# 18650_13s8p.net
KiCad netlist of a schematic drawn in Altium Designer
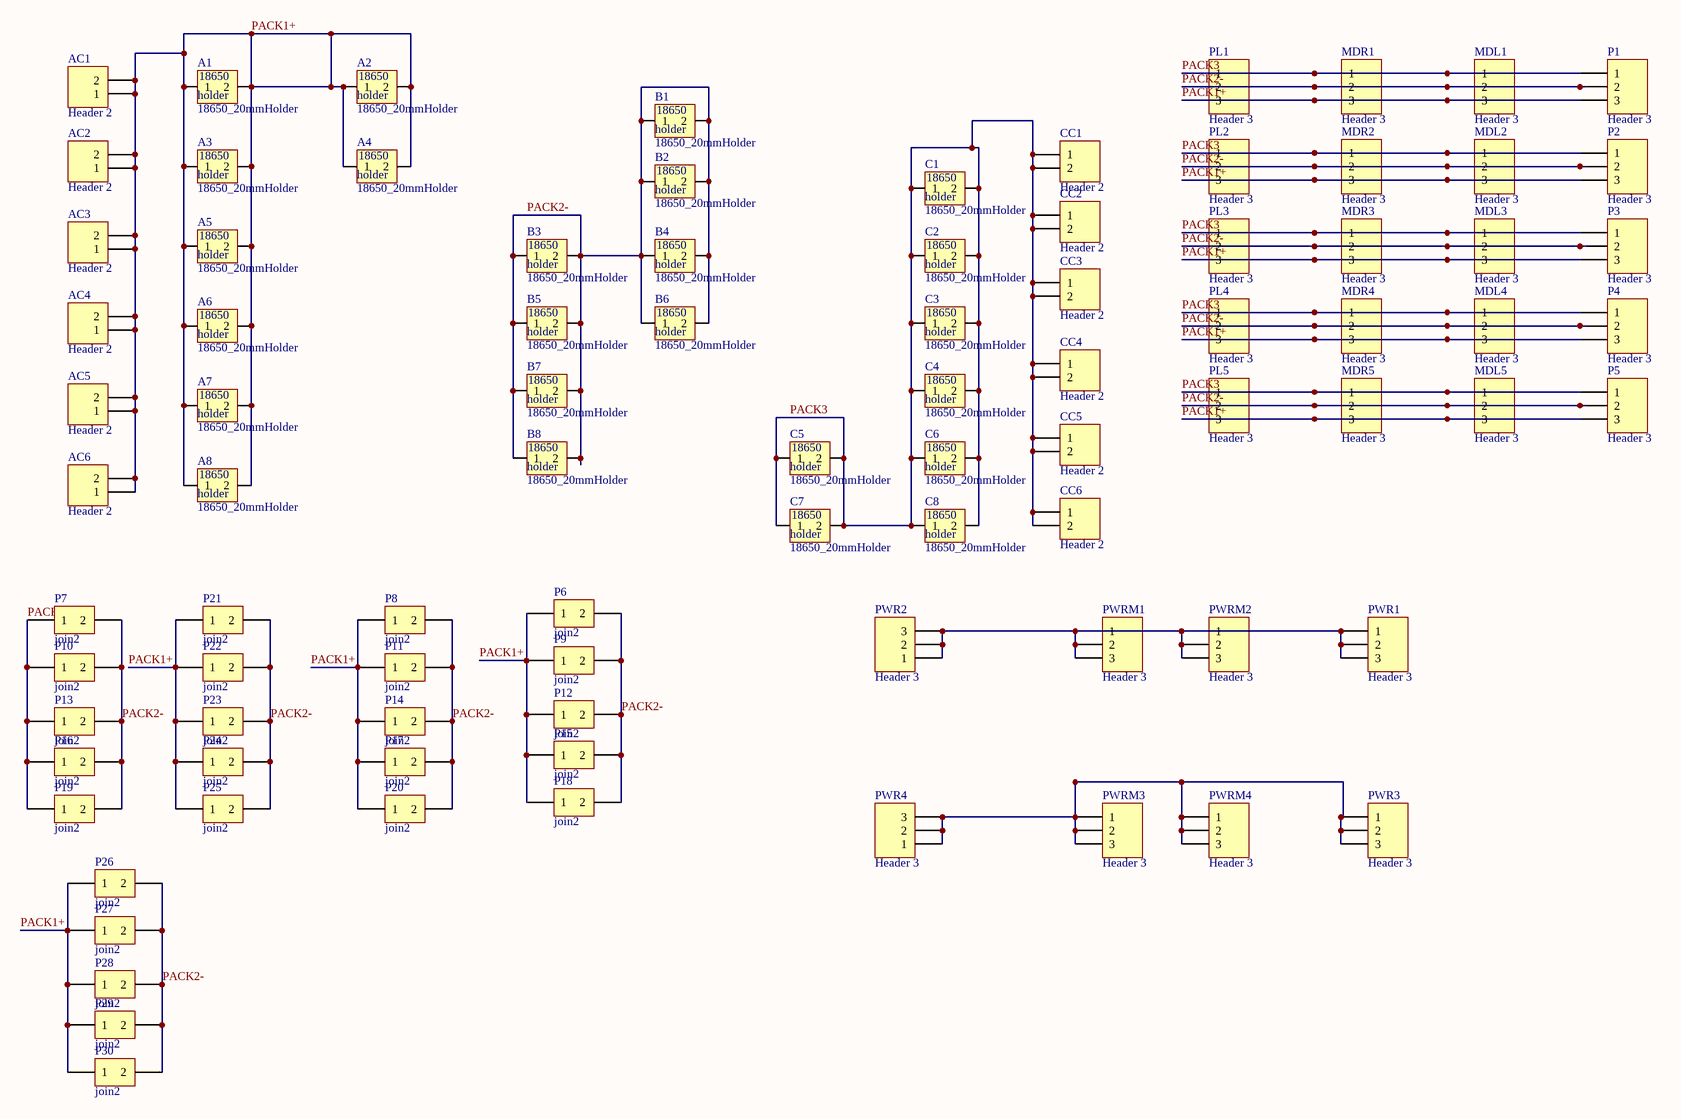
[diagram p0: 18650_13s8p.SchDoc]

(export (version "E")
  (design (tool "Eeschema 10.0.6"))
  (components
    (comp (ref "A1")
      (value "18650_20mmHolder")
      (footprint "18650holder20_2")
      (description "20mm holder 18650 sujungimai tiek - tiek pliuso")
      (fields (field (name "PUBLISHER") "Altium Limited"))
      (libsource (lib "Mechaniniai") (part "18650_20mmHolder"))
    )
    (comp (ref "A2")
      (value "18650_20mmHolder")
      (footprint "18650holder20_2")
      (description "20mm holder 18650 sujungimai tiek - tiek pliuso")
      (fields (field (name "PUBLISHER") "Altium Limited"))
      (libsource (lib "Mechaniniai") (part "18650_20mmHolder"))
    )
    (comp (ref "A3")
      (value "18650_20mmHolder")
      (footprint "18650holder20_2")
      (description "20mm holder 18650 sujungimai tiek - tiek pliuso")
      (fields (field (name "PUBLISHER") "Altium Limited"))
      (libsource (lib "Mechaniniai") (part "18650_20mmHolder"))
    )
    (comp (ref "A4")
      (value "18650_20mmHolder")
      (footprint "18650holder20_2")
      (description "20mm holder 18650 sujungimai tiek - tiek pliuso")
      (fields (field (name "PUBLISHER") "Altium Limited"))
      (libsource (lib "Mechaniniai") (part "18650_20mmHolder"))
    )
    (comp (ref "A5")
      (value "18650_20mmHolder")
      (footprint "18650holder20_2")
      (description "20mm holder 18650 sujungimai tiek - tiek pliuso")
      (fields (field (name "PUBLISHER") "Altium Limited"))
      (libsource (lib "Mechaniniai") (part "18650_20mmHolder"))
    )
    (comp (ref "A6")
      (value "18650_20mmHolder")
      (footprint "18650holder20_2")
      (description "20mm holder 18650 sujungimai tiek - tiek pliuso")
      (fields (field (name "PUBLISHER") "Altium Limited"))
      (libsource (lib "Mechaniniai") (part "18650_20mmHolder"))
    )
    (comp (ref "A7")
      (value "18650_20mmHolder")
      (footprint "18650holder20_2")
      (description "20mm holder 18650 sujungimai tiek - tiek pliuso")
      (fields (field (name "PUBLISHER") "Altium Limited"))
      (libsource (lib "Mechaniniai") (part "18650_20mmHolder"))
    )
    (comp (ref "A8")
      (value "18650_20mmHolder")
      (footprint "18650holder20_2")
      (description "20mm holder 18650 sujungimai tiek - tiek pliuso")
      (fields (field (name "PUBLISHER") "Altium Limited"))
      (libsource (lib "Mechaniniai") (part "18650_20mmHolder"))
    )
    (comp (ref "AC1")
      (value "Header 2")
      (footprint "HDR1X2")
      (description "Header, 2-Pin")
      (fields (field (name "PUBLISHER") "Altium Limited"))
      (libsource (lib "") (part "Header 2_1"))
    )
    (comp (ref "AC2")
      (value "Header 2")
      (footprint "HDR1X2")
      (description "Header, 2-Pin")
      (fields (field (name "PUBLISHER") "Altium Limited"))
      (libsource (lib "") (part "Header 2_1"))
    )
    (comp (ref "AC3")
      (value "Header 2")
      (footprint "HDR1X2")
      (description "Header, 2-Pin")
      (fields (field (name "PUBLISHER") "Altium Limited"))
      (libsource (lib "") (part "Header 2_1"))
    )
    (comp (ref "AC4")
      (value "Header 2")
      (footprint "HDR1X2")
      (description "Header, 2-Pin")
      (fields (field (name "PUBLISHER") "Altium Limited"))
      (libsource (lib "") (part "Header 2_1"))
    )
    (comp (ref "AC5")
      (value "Header 2")
      (footprint "HDR1X2")
      (description "Header, 2-Pin")
      (fields (field (name "PUBLISHER") "Altium Limited"))
      (libsource (lib "") (part "Header 2_1"))
    )
    (comp (ref "AC6")
      (value "Header 2")
      (footprint "HDR1X2")
      (description "Header, 2-Pin")
      (fields (field (name "PUBLISHER") "Altium Limited"))
      (libsource (lib "") (part "Header 2_1"))
    )
    (comp (ref "B1")
      (value "18650_20mmHolder")
      (footprint "18650holder20_2")
      (description "20mm holder 18650 sujungimai tiek - tiek pliuso")
      (fields (field (name "PUBLISHER") "Altium Limited"))
      (libsource (lib "Mechaniniai") (part "18650_20mmHolder"))
    )
    (comp (ref "B2")
      (value "18650_20mmHolder")
      (footprint "18650holder20_2")
      (description "20mm holder 18650 sujungimai tiek - tiek pliuso")
      (fields (field (name "PUBLISHER") "Altium Limited"))
      (libsource (lib "Mechaniniai") (part "18650_20mmHolder"))
    )
    (comp (ref "B3")
      (value "18650_20mmHolder")
      (footprint "18650holder20_2")
      (description "20mm holder 18650 sujungimai tiek - tiek pliuso")
      (fields (field (name "PUBLISHER") "Altium Limited"))
      (libsource (lib "Mechaniniai") (part "18650_20mmHolder"))
    )
    (comp (ref "B4")
      (value "18650_20mmHolder")
      (footprint "18650holder20_2")
      (description "20mm holder 18650 sujungimai tiek - tiek pliuso")
      (fields (field (name "PUBLISHER") "Altium Limited"))
      (libsource (lib "Mechaniniai") (part "18650_20mmHolder"))
    )
    (comp (ref "B5")
      (value "18650_20mmHolder")
      (footprint "18650holder20_2")
      (description "20mm holder 18650 sujungimai tiek - tiek pliuso")
      (fields (field (name "PUBLISHER") "Altium Limited"))
      (libsource (lib "Mechaniniai") (part "18650_20mmHolder"))
    )
    (comp (ref "B6")
      (value "18650_20mmHolder")
      (footprint "18650holder20_2")
      (description "20mm holder 18650 sujungimai tiek - tiek pliuso")
      (fields (field (name "PUBLISHER") "Altium Limited"))
      (libsource (lib "Mechaniniai") (part "18650_20mmHolder"))
    )
    (comp (ref "B7")
      (value "18650_20mmHolder")
      (footprint "18650holder20_2")
      (description "20mm holder 18650 sujungimai tiek - tiek pliuso")
      (fields (field (name "PUBLISHER") "Altium Limited"))
      (libsource (lib "Mechaniniai") (part "18650_20mmHolder"))
    )
    (comp (ref "B8")
      (value "18650_20mmHolder")
      (footprint "18650holder20_2")
      (description "20mm holder 18650 sujungimai tiek - tiek pliuso")
      (fields (field (name "PUBLISHER") "Altium Limited"))
      (libsource (lib "Mechaniniai") (part "18650_20mmHolder"))
    )
    (comp (ref "C1")
      (value "18650_20mmHolder")
      (footprint "18650holder20_2")
      (description "20mm holder 18650 sujungimai tiek - tiek pliuso")
      (fields (field (name "PUBLISHER") "Altium Limited"))
      (libsource (lib "Mechaniniai") (part "18650_20mmHolder"))
    )
    (comp (ref "C2")
      (value "18650_20mmHolder")
      (footprint "18650holder20_2")
      (description "20mm holder 18650 sujungimai tiek - tiek pliuso")
      (fields (field (name "PUBLISHER") "Altium Limited"))
      (libsource (lib "Mechaniniai") (part "18650_20mmHolder"))
    )
    (comp (ref "C3")
      (value "18650_20mmHolder")
      (footprint "18650holder20_2")
      (description "20mm holder 18650 sujungimai tiek - tiek pliuso")
      (fields (field (name "PUBLISHER") "Altium Limited"))
      (libsource (lib "Mechaniniai") (part "18650_20mmHolder"))
    )
    (comp (ref "C4")
      (value "18650_20mmHolder")
      (footprint "18650holder20_2")
      (description "20mm holder 18650 sujungimai tiek - tiek pliuso")
      (fields (field (name "PUBLISHER") "Altium Limited"))
      (libsource (lib "Mechaniniai") (part "18650_20mmHolder"))
    )
    (comp (ref "C5")
      (value "18650_20mmHolder")
      (footprint "18650holder20_2")
      (description "20mm holder 18650 sujungimai tiek - tiek pliuso")
      (fields (field (name "PUBLISHER") "Altium Limited"))
      (libsource (lib "Mechaniniai") (part "18650_20mmHolder"))
    )
    (comp (ref "C6")
      (value "18650_20mmHolder")
      (footprint "18650holder20_2")
      (description "20mm holder 18650 sujungimai tiek - tiek pliuso")
      (fields (field (name "PUBLISHER") "Altium Limited"))
      (libsource (lib "Mechaniniai") (part "18650_20mmHolder"))
    )
    (comp (ref "C7")
      (value "18650_20mmHolder")
      (footprint "18650holder20_2")
      (description "20mm holder 18650 sujungimai tiek - tiek pliuso")
      (fields (field (name "PUBLISHER") "Altium Limited"))
      (libsource (lib "Mechaniniai") (part "18650_20mmHolder"))
    )
    (comp (ref "C8")
      (value "18650_20mmHolder")
      (footprint "18650holder20_2")
      (description "20mm holder 18650 sujungimai tiek - tiek pliuso")
      (fields (field (name "PUBLISHER") "Altium Limited"))
      (libsource (lib "Mechaniniai") (part "18650_20mmHolder"))
    )
    (comp (ref "CC1")
      (value "Header 2")
      (footprint "HDR1X2")
      (description "Header, 2-Pin")
      (fields (field (name "PUBLISHER") "Altium Limited"))
      (libsource (lib "PIN_HEADER") (part "Header 2"))
    )
    (comp (ref "CC2")
      (value "Header 2")
      (footprint "HDR1X2")
      (description "Header, 2-Pin")
      (fields (field (name "PUBLISHER") "Altium Limited"))
      (libsource (lib "PIN_HEADER") (part "Header 2"))
    )
    (comp (ref "CC3")
      (value "Header 2")
      (footprint "HDR1X2")
      (description "Header, 2-Pin")
      (fields (field (name "PUBLISHER") "Altium Limited"))
      (libsource (lib "PIN_HEADER") (part "Header 2"))
    )
    (comp (ref "CC4")
      (value "Header 2")
      (footprint "HDR1X2")
      (description "Header, 2-Pin")
      (fields (field (name "PUBLISHER") "Altium Limited"))
      (libsource (lib "PIN_HEADER") (part "Header 2"))
    )
    (comp (ref "CC5")
      (value "Header 2")
      (footprint "HDR1X2")
      (description "Header, 2-Pin")
      (fields (field (name "PUBLISHER") "Altium Limited"))
      (libsource (lib "PIN_HEADER") (part "Header 2"))
    )
    (comp (ref "CC6")
      (value "Header 2")
      (footprint "HDR1X2")
      (description "Header, 2-Pin")
      (fields (field (name "PUBLISHER") "Altium Limited"))
      (libsource (lib "PIN_HEADER") (part "Header 2"))
    )
    (comp (ref "MDL1")
      (value "Header 3")
      (footprint "HDR1X3")
      (description "Header, 3-Pin")
      (fields (field (name "PUBLISHER") "Altium Limited"))
      (libsource (lib "PIN_HEADER") (part "Header 3"))
    )
    (comp (ref "MDL2")
      (value "Header 3")
      (footprint "HDR1X3")
      (description "Header, 3-Pin")
      (fields (field (name "PUBLISHER") "Altium Limited"))
      (libsource (lib "PIN_HEADER") (part "Header 3"))
    )
    (comp (ref "MDL3")
      (value "Header 3")
      (footprint "HDR1X3")
      (description "Header, 3-Pin")
      (fields (field (name "PUBLISHER") "Altium Limited"))
      (libsource (lib "PIN_HEADER") (part "Header 3"))
    )
    (comp (ref "MDL4")
      (value "Header 3")
      (footprint "HDR1X3")
      (description "Header, 3-Pin")
      (fields (field (name "PUBLISHER") "Altium Limited"))
      (libsource (lib "PIN_HEADER") (part "Header 3"))
    )
    (comp (ref "MDL5")
      (value "Header 3")
      (footprint "HDR1X3")
      (description "Header, 3-Pin")
      (fields (field (name "PUBLISHER") "Altium Limited"))
      (libsource (lib "PIN_HEADER") (part "Header 3"))
    )
    (comp (ref "MDR1")
      (value "Header 3")
      (footprint "HDR1X3")
      (description "Header, 3-Pin")
      (fields (field (name "PUBLISHER") "Altium Limited"))
      (libsource (lib "PIN_HEADER") (part "Header 3"))
    )
    (comp (ref "MDR2")
      (value "Header 3")
      (footprint "HDR1X3")
      (description "Header, 3-Pin")
      (fields (field (name "PUBLISHER") "Altium Limited"))
      (libsource (lib "PIN_HEADER") (part "Header 3"))
    )
    (comp (ref "MDR3")
      (value "Header 3")
      (footprint "HDR1X3")
      (description "Header, 3-Pin")
      (fields (field (name "PUBLISHER") "Altium Limited"))
      (libsource (lib "PIN_HEADER") (part "Header 3"))
    )
    (comp (ref "MDR4")
      (value "Header 3")
      (footprint "HDR1X3")
      (description "Header, 3-Pin")
      (fields (field (name "PUBLISHER") "Altium Limited"))
      (libsource (lib "PIN_HEADER") (part "Header 3"))
    )
    (comp (ref "MDR5")
      (value "Header 3")
      (footprint "HDR1X3")
      (description "Header, 3-Pin")
      (fields (field (name "PUBLISHER") "Altium Limited"))
      (libsource (lib "PIN_HEADER") (part "Header 3"))
    )
    (comp (ref "P1")
      (value "Header 3")
      (footprint "HDR1X3")
      (description "Header, 3-Pin")
      (fields (field (name "PUBLISHER") "Altium Limited"))
      (libsource (lib "PIN_HEADER") (part "Header 3"))
    )
    (comp (ref "P2")
      (value "Header 3")
      (footprint "HDR1X3")
      (description "Header, 3-Pin")
      (fields (field (name "PUBLISHER") "Altium Limited"))
      (libsource (lib "PIN_HEADER") (part "Header 3"))
    )
    (comp (ref "P3")
      (value "Header 3")
      (footprint "HDR1X3")
      (description "Header, 3-Pin")
      (fields (field (name "PUBLISHER") "Altium Limited"))
      (libsource (lib "PIN_HEADER") (part "Header 3"))
    )
    (comp (ref "P4")
      (value "Header 3")
      (footprint "HDR1X3")
      (description "Header, 3-Pin")
      (fields (field (name "PUBLISHER") "Altium Limited"))
      (libsource (lib "PIN_HEADER") (part "Header 3"))
    )
    (comp (ref "P5")
      (value "Header 3")
      (footprint "HDR1X3")
      (description "Header, 3-Pin")
      (fields (field (name "PUBLISHER") "Altium Limited"))
      (libsource (lib "PIN_HEADER") (part "Header 3"))
    )
    (comp (ref "P6")
      (value "join2")
      (footprint "join2_0603")
      (description "Header, 2-Pin")
      (fields (field (name "PUBLISHER") "Altium Limited"))
      (libsource (lib "PIN_HEADER") (part "join2"))
    )
    (comp (ref "P7")
      (value "join2")
      (footprint "join2_0603")
      (description "Header, 2-Pin")
      (fields (field (name "PUBLISHER") "Altium Limited"))
      (libsource (lib "PIN_HEADER") (part "join2"))
    )
    (comp (ref "P8")
      (value "join2")
      (footprint "join2_0603")
      (description "Header, 2-Pin")
      (fields (field (name "PUBLISHER") "Altium Limited"))
      (libsource (lib "PIN_HEADER") (part "join2"))
    )
    (comp (ref "P9")
      (value "join2")
      (footprint "join2_0603")
      (description "Header, 2-Pin")
      (fields (field (name "PUBLISHER") "Altium Limited"))
      (libsource (lib "PIN_HEADER") (part "join2"))
    )
    (comp (ref "P10")
      (value "join2")
      (footprint "join2_0603")
      (description "Header, 2-Pin")
      (fields (field (name "PUBLISHER") "Altium Limited"))
      (libsource (lib "PIN_HEADER") (part "join2"))
    )
    (comp (ref "P11")
      (value "join2")
      (footprint "join2_0603")
      (description "Header, 2-Pin")
      (fields (field (name "PUBLISHER") "Altium Limited"))
      (libsource (lib "PIN_HEADER") (part "join2"))
    )
    (comp (ref "P12")
      (value "join2")
      (footprint "join2_0603")
      (description "Header, 2-Pin")
      (fields (field (name "PUBLISHER") "Altium Limited"))
      (libsource (lib "PIN_HEADER") (part "join2"))
    )
    (comp (ref "P13")
      (value "join2")
      (footprint "join2_0603")
      (description "Header, 2-Pin")
      (fields (field (name "PUBLISHER") "Altium Limited"))
      (libsource (lib "PIN_HEADER") (part "join2"))
    )
    (comp (ref "P14")
      (value "join2")
      (footprint "join2_0603")
      (description "Header, 2-Pin")
      (fields (field (name "PUBLISHER") "Altium Limited"))
      (libsource (lib "PIN_HEADER") (part "join2"))
    )
    (comp (ref "P15")
      (value "join2")
      (footprint "join2_0603")
      (description "Header, 2-Pin")
      (fields (field (name "PUBLISHER") "Altium Limited"))
      (libsource (lib "PIN_HEADER") (part "join2"))
    )
    (comp (ref "P16")
      (value "join2")
      (footprint "join2_0603")
      (description "Header, 2-Pin")
      (fields (field (name "PUBLISHER") "Altium Limited"))
      (libsource (lib "PIN_HEADER") (part "join2"))
    )
    (comp (ref "P17")
      (value "join2")
      (footprint "join2_0603")
      (description "Header, 2-Pin")
      (fields (field (name "PUBLISHER") "Altium Limited"))
      (libsource (lib "PIN_HEADER") (part "join2"))
    )
    (comp (ref "P18")
      (value "join2")
      (footprint "join2_0603")
      (description "Header, 2-Pin")
      (fields (field (name "PUBLISHER") "Altium Limited"))
      (libsource (lib "PIN_HEADER") (part "join2"))
    )
    (comp (ref "P19")
      (value "join2")
      (footprint "join2_0603")
      (description "Header, 2-Pin")
      (fields (field (name "PUBLISHER") "Altium Limited"))
      (libsource (lib "PIN_HEADER") (part "join2"))
    )
    (comp (ref "P20")
      (value "join2")
      (footprint "join2_0603")
      (description "Header, 2-Pin")
      (fields (field (name "PUBLISHER") "Altium Limited"))
      (libsource (lib "PIN_HEADER") (part "join2"))
    )
    (comp (ref "P21")
      (value "join2")
      (footprint "join2_0603")
      (description "Header, 2-Pin")
      (fields (field (name "PUBLISHER") "Altium Limited"))
      (libsource (lib "PIN_HEADER") (part "join2"))
    )
    (comp (ref "P22")
      (value "join2")
      (footprint "join2_0603")
      (description "Header, 2-Pin")
      (fields (field (name "PUBLISHER") "Altium Limited"))
      (libsource (lib "PIN_HEADER") (part "join2"))
    )
    (comp (ref "P23")
      (value "join2")
      (footprint "join2_0603")
      (description "Header, 2-Pin")
      (fields (field (name "PUBLISHER") "Altium Limited"))
      (libsource (lib "PIN_HEADER") (part "join2"))
    )
    (comp (ref "P24")
      (value "join2")
      (footprint "join2_0603")
      (description "Header, 2-Pin")
      (fields (field (name "PUBLISHER") "Altium Limited"))
      (libsource (lib "PIN_HEADER") (part "join2"))
    )
    (comp (ref "P25")
      (value "join2")
      (footprint "join2_0603")
      (description "Header, 2-Pin")
      (fields (field (name "PUBLISHER") "Altium Limited"))
      (libsource (lib "PIN_HEADER") (part "join2"))
    )
    (comp (ref "P26")
      (value "join2")
      (footprint "join2_0603")
      (description "Header, 2-Pin")
      (fields (field (name "PUBLISHER") "Altium Limited"))
      (libsource (lib "PIN_HEADER") (part "join2"))
    )
    (comp (ref "P27")
      (value "join2")
      (footprint "join2_0603")
      (description "Header, 2-Pin")
      (fields (field (name "PUBLISHER") "Altium Limited"))
      (libsource (lib "PIN_HEADER") (part "join2"))
    )
    (comp (ref "P28")
      (value "join2")
      (footprint "join2_0603")
      (description "Header, 2-Pin")
      (fields (field (name "PUBLISHER") "Altium Limited"))
      (libsource (lib "PIN_HEADER") (part "join2"))
    )
    (comp (ref "P29")
      (value "join2")
      (footprint "join2_0603")
      (description "Header, 2-Pin")
      (fields (field (name "PUBLISHER") "Altium Limited"))
      (libsource (lib "PIN_HEADER") (part "join2"))
    )
    (comp (ref "P30")
      (value "join2")
      (footprint "join2_0603")
      (description "Header, 2-Pin")
      (fields (field (name "PUBLISHER") "Altium Limited"))
      (libsource (lib "PIN_HEADER") (part "join2"))
    )
    (comp (ref "PL1")
      (value "Header 3")
      (footprint "HDR1X3")
      (description "Header, 3-Pin")
      (fields (field (name "PUBLISHER") "Altium Limited"))
      (libsource (lib "PIN_HEADER") (part "Header 3"))
    )
    (comp (ref "PL2")
      (value "Header 3")
      (footprint "HDR1X3")
      (description "Header, 3-Pin")
      (fields (field (name "PUBLISHER") "Altium Limited"))
      (libsource (lib "PIN_HEADER") (part "Header 3"))
    )
    (comp (ref "PL3")
      (value "Header 3")
      (footprint "HDR1X3")
      (description "Header, 3-Pin")
      (fields (field (name "PUBLISHER") "Altium Limited"))
      (libsource (lib "PIN_HEADER") (part "Header 3"))
    )
    (comp (ref "PL4")
      (value "Header 3")
      (footprint "HDR1X3")
      (description "Header, 3-Pin")
      (fields (field (name "PUBLISHER") "Altium Limited"))
      (libsource (lib "PIN_HEADER") (part "Header 3"))
    )
    (comp (ref "PL5")
      (value "Header 3")
      (footprint "HDR1X3")
      (description "Header, 3-Pin")
      (fields (field (name "PUBLISHER") "Altium Limited"))
      (libsource (lib "PIN_HEADER") (part "Header 3"))
    )
    (comp (ref "PWR1")
      (value "Header 3")
      (footprint "HDR1X3")
      (description "Header, 3-Pin")
      (fields (field (name "PUBLISHER") "Altium Limited"))
      (libsource (lib "PIN_HEADER") (part "Header 3"))
    )
    (comp (ref "PWR2")
      (value "Header 3")
      (footprint "HDR1X3")
      (description "Header, 3-Pin")
      (fields (field (name "PUBLISHER") "Altium Limited"))
      (libsource (lib "") (part "Header 3_1"))
    )
    (comp (ref "PWR3")
      (value "Header 3")
      (footprint "HDR1X3")
      (description "Header, 3-Pin")
      (fields (field (name "PUBLISHER") "Altium Limited"))
      (libsource (lib "PIN_HEADER") (part "Header 3"))
    )
    (comp (ref "PWR4")
      (value "Header 3")
      (footprint "HDR1X3")
      (description "Header, 3-Pin")
      (fields (field (name "PUBLISHER") "Altium Limited"))
      (libsource (lib "") (part "Header 3_1"))
    )
    (comp (ref "PWRM1")
      (value "Header 3")
      (footprint "HDR1X3")
      (description "Header, 3-Pin")
      (fields (field (name "PUBLISHER") "Altium Limited"))
      (libsource (lib "PIN_HEADER") (part "Header 3"))
    )
    (comp (ref "PWRM2")
      (value "Header 3")
      (footprint "HDR1X3")
      (description "Header, 3-Pin")
      (fields (field (name "PUBLISHER") "Altium Limited"))
      (libsource (lib "PIN_HEADER") (part "Header 3"))
    )
    (comp (ref "PWRM3")
      (value "Header 3")
      (footprint "HDR1X3")
      (description "Header, 3-Pin")
      (fields (field (name "PUBLISHER") "Altium Limited"))
      (libsource (lib "PIN_HEADER") (part "Header 3"))
    )
    (comp (ref "PWRM4")
      (value "Header 3")
      (footprint "HDR1X3")
      (description "Header, 3-Pin")
      (fields (field (name "PUBLISHER") "Altium Limited"))
      (libsource (lib "PIN_HEADER") (part "Header 3"))
    )
  )
  (nets
    (net (code "1") (name "/PACK1+") (class "Default")
      (node (ref "A1") (pin "1") (pinfunction "1_1") (pintype "passive"))
      (node (ref "A1") (pin "2") (pinfunction "2_2") (pintype "passive"))
      (node (ref "A2") (pin "1") (pinfunction "1_1") (pintype "passive"))
      (node (ref "A2") (pin "2") (pinfunction "2_2") (pintype "passive"))
      (node (ref "A3") (pin "1") (pinfunction "1_1") (pintype "passive"))
      (node (ref "A3") (pin "2") (pinfunction "2_2") (pintype "passive"))
      (node (ref "A4") (pin "1") (pinfunction "1_1") (pintype "passive"))
      (node (ref "A4") (pin "2") (pinfunction "2_2") (pintype "passive"))
      (node (ref "A5") (pin "1") (pinfunction "1_1") (pintype "passive"))
      (node (ref "A5") (pin "2") (pinfunction "2_2") (pintype "passive"))
      (node (ref "A6") (pin "1") (pinfunction "1_1") (pintype "passive"))
      (node (ref "A6") (pin "2") (pinfunction "2_2") (pintype "passive"))
      (node (ref "A7") (pin "1") (pinfunction "1_1") (pintype "passive"))
      (node (ref "A7") (pin "2") (pinfunction "2_2") (pintype "passive"))
      (node (ref "A8") (pin "1") (pinfunction "1_1") (pintype "passive"))
      (node (ref "A8") (pin "2") (pinfunction "2_2") (pintype "passive"))
      (node (ref "AC1") (pin "1") (pinfunction "1_1") (pintype "passive"))
      (node (ref "AC1") (pin "2") (pinfunction "2_2") (pintype "passive"))
      (node (ref "AC2") (pin "1") (pinfunction "1_1") (pintype "passive"))
      (node (ref "AC2") (pin "2") (pinfunction "2_2") (pintype "passive"))
      (node (ref "AC3") (pin "1") (pinfunction "1_1") (pintype "passive"))
      (node (ref "AC3") (pin "2") (pinfunction "2_2") (pintype "passive"))
      (node (ref "AC4") (pin "1") (pinfunction "1_1") (pintype "passive"))
      (node (ref "AC4") (pin "2") (pinfunction "2_2") (pintype "passive"))
      (node (ref "AC5") (pin "1") (pinfunction "1_1") (pintype "passive"))
      (node (ref "AC5") (pin "2") (pinfunction "2_2") (pintype "passive"))
      (node (ref "AC6") (pin "1") (pinfunction "1_1") (pintype "passive"))
      (node (ref "AC6") (pin "2") (pinfunction "2_2") (pintype "passive"))
      (node (ref "MDL1") (pin "3") (pinfunction "3_3") (pintype "passive"))
      (node (ref "MDL2") (pin "3") (pinfunction "3_3") (pintype "passive"))
      (node (ref "MDL3") (pin "3") (pinfunction "3_3") (pintype "passive"))
      (node (ref "MDL4") (pin "3") (pinfunction "3_3") (pintype "passive"))
      (node (ref "MDL5") (pin "3") (pinfunction "3_3") (pintype "passive"))
      (node (ref "MDR1") (pin "3") (pinfunction "3_3") (pintype "passive"))
      (node (ref "MDR2") (pin "3") (pinfunction "3_3") (pintype "passive"))
      (node (ref "MDR3") (pin "3") (pinfunction "3_3") (pintype "passive"))
      (node (ref "MDR4") (pin "3") (pinfunction "3_3") (pintype "passive"))
      (node (ref "MDR5") (pin "3") (pinfunction "3_3") (pintype "passive"))
      (node (ref "P1") (pin "3") (pinfunction "3_3") (pintype "passive"))
      (node (ref "P10") (pin "1") (pinfunction "1_1") (pintype "passive"))
      (node (ref "P11") (pin "1") (pinfunction "1_1") (pintype "passive"))
      (node (ref "P12") (pin "1") (pinfunction "1_1") (pintype "passive"))
      (node (ref "P13") (pin "1") (pinfunction "1_1") (pintype "passive"))
      (node (ref "P14") (pin "1") (pinfunction "1_1") (pintype "passive"))
      (node (ref "P15") (pin "1") (pinfunction "1_1") (pintype "passive"))
      (node (ref "P16") (pin "1") (pinfunction "1_1") (pintype "passive"))
      (node (ref "P17") (pin "1") (pinfunction "1_1") (pintype "passive"))
      (node (ref "P18") (pin "1") (pinfunction "1_1") (pintype "passive"))
      (node (ref "P19") (pin "1") (pinfunction "1_1") (pintype "passive"))
      (node (ref "P2") (pin "3") (pinfunction "3_3") (pintype "passive"))
      (node (ref "P20") (pin "1") (pinfunction "1_1") (pintype "passive"))
      (node (ref "P21") (pin "1") (pinfunction "1_1") (pintype "passive"))
      (node (ref "P22") (pin "1") (pinfunction "1_1") (pintype "passive"))
      (node (ref "P23") (pin "1") (pinfunction "1_1") (pintype "passive"))
      (node (ref "P24") (pin "1") (pinfunction "1_1") (pintype "passive"))
      (node (ref "P25") (pin "1") (pinfunction "1_1") (pintype "passive"))
      (node (ref "P26") (pin "1") (pinfunction "1_1") (pintype "passive"))
      (node (ref "P27") (pin "1") (pinfunction "1_1") (pintype "passive"))
      (node (ref "P28") (pin "1") (pinfunction "1_1") (pintype "passive"))
      (node (ref "P29") (pin "1") (pinfunction "1_1") (pintype "passive"))
      (node (ref "P3") (pin "3") (pinfunction "3_3") (pintype "passive"))
      (node (ref "P30") (pin "1") (pinfunction "1_1") (pintype "passive"))
      (node (ref "P4") (pin "3") (pinfunction "3_3") (pintype "passive"))
      (node (ref "P5") (pin "3") (pinfunction "3_3") (pintype "passive"))
      (node (ref "P6") (pin "1") (pinfunction "1_1") (pintype "passive"))
      (node (ref "P7") (pin "1") (pinfunction "1_1") (pintype "passive"))
      (node (ref "P8") (pin "1") (pinfunction "1_1") (pintype "passive"))
      (node (ref "P9") (pin "1") (pinfunction "1_1") (pintype "passive"))
      (node (ref "PL1") (pin "3") (pinfunction "3_3") (pintype "passive"))
      (node (ref "PL2") (pin "3") (pinfunction "3_3") (pintype "passive"))
      (node (ref "PL3") (pin "3") (pinfunction "3_3") (pintype "passive"))
      (node (ref "PL4") (pin "3") (pinfunction "3_3") (pintype "passive"))
      (node (ref "PL5") (pin "3") (pinfunction "3_3") (pintype "passive"))
    )
    (net (code "2") (name "/PACK2-") (class "Default")
      (node (ref "B1") (pin "1") (pinfunction "1_1") (pintype "passive"))
      (node (ref "B1") (pin "2") (pinfunction "2_2") (pintype "passive"))
      (node (ref "B2") (pin "1") (pinfunction "1_1") (pintype "passive"))
      (node (ref "B2") (pin "2") (pinfunction "2_2") (pintype "passive"))
      (node (ref "B3") (pin "1") (pinfunction "1_1") (pintype "passive"))
      (node (ref "B3") (pin "2") (pinfunction "2_2") (pintype "passive"))
      (node (ref "B4") (pin "1") (pinfunction "1_1") (pintype "passive"))
      (node (ref "B4") (pin "2") (pinfunction "2_2") (pintype "passive"))
      (node (ref "B5") (pin "1") (pinfunction "1_1") (pintype "passive"))
      (node (ref "B5") (pin "2") (pinfunction "2_2") (pintype "passive"))
      (node (ref "B6") (pin "1") (pinfunction "1_1") (pintype "passive"))
      (node (ref "B6") (pin "2") (pinfunction "2_2") (pintype "passive"))
      (node (ref "B7") (pin "1") (pinfunction "1_1") (pintype "passive"))
      (node (ref "B7") (pin "2") (pinfunction "2_2") (pintype "passive"))
      (node (ref "B8") (pin "1") (pinfunction "1_1") (pintype "passive"))
      (node (ref "B8") (pin "2") (pinfunction "2_2") (pintype "passive"))
      (node (ref "MDL1") (pin "2") (pinfunction "2_2") (pintype "passive"))
      (node (ref "MDL2") (pin "2") (pinfunction "2_2") (pintype "passive"))
      (node (ref "MDL3") (pin "2") (pinfunction "2_2") (pintype "passive"))
      (node (ref "MDL4") (pin "2") (pinfunction "2_2") (pintype "passive"))
      (node (ref "MDL5") (pin "2") (pinfunction "2_2") (pintype "passive"))
      (node (ref "MDR1") (pin "2") (pinfunction "2_2") (pintype "passive"))
      (node (ref "MDR2") (pin "2") (pinfunction "2_2") (pintype "passive"))
      (node (ref "MDR3") (pin "2") (pinfunction "2_2") (pintype "passive"))
      (node (ref "MDR4") (pin "2") (pinfunction "2_2") (pintype "passive"))
      (node (ref "MDR5") (pin "2") (pinfunction "2_2") (pintype "passive"))
      (node (ref "P1") (pin "2") (pinfunction "2_2") (pintype "passive"))
      (node (ref "P10") (pin "2") (pinfunction "2_2") (pintype "passive"))
      (node (ref "P11") (pin "2") (pinfunction "2_2") (pintype "passive"))
      (node (ref "P12") (pin "2") (pinfunction "2_2") (pintype "passive"))
      (node (ref "P13") (pin "2") (pinfunction "2_2") (pintype "passive"))
      (node (ref "P14") (pin "2") (pinfunction "2_2") (pintype "passive"))
      (node (ref "P15") (pin "2") (pinfunction "2_2") (pintype "passive"))
      (node (ref "P16") (pin "2") (pinfunction "2_2") (pintype "passive"))
      (node (ref "P17") (pin "2") (pinfunction "2_2") (pintype "passive"))
      (node (ref "P18") (pin "2") (pinfunction "2_2") (pintype "passive"))
      (node (ref "P19") (pin "2") (pinfunction "2_2") (pintype "passive"))
      (node (ref "P2") (pin "2") (pinfunction "2_2") (pintype "passive"))
      (node (ref "P20") (pin "2") (pinfunction "2_2") (pintype "passive"))
      (node (ref "P21") (pin "2") (pinfunction "2_2") (pintype "passive"))
      (node (ref "P22") (pin "2") (pinfunction "2_2") (pintype "passive"))
      (node (ref "P23") (pin "2") (pinfunction "2_2") (pintype "passive"))
      (node (ref "P24") (pin "2") (pinfunction "2_2") (pintype "passive"))
      (node (ref "P25") (pin "2") (pinfunction "2_2") (pintype "passive"))
      (node (ref "P26") (pin "2") (pinfunction "2_2") (pintype "passive"))
      (node (ref "P27") (pin "2") (pinfunction "2_2") (pintype "passive"))
      (node (ref "P28") (pin "2") (pinfunction "2_2") (pintype "passive"))
      (node (ref "P29") (pin "2") (pinfunction "2_2") (pintype "passive"))
      (node (ref "P3") (pin "2") (pinfunction "2_2") (pintype "passive"))
      (node (ref "P30") (pin "2") (pinfunction "2_2") (pintype "passive"))
      (node (ref "P4") (pin "2") (pinfunction "2_2") (pintype "passive"))
      (node (ref "P5") (pin "2") (pinfunction "2_2") (pintype "passive"))
      (node (ref "P6") (pin "2") (pinfunction "2_2") (pintype "passive"))
      (node (ref "P7") (pin "2") (pinfunction "2_2") (pintype "passive"))
      (node (ref "P8") (pin "2") (pinfunction "2_2") (pintype "passive"))
      (node (ref "P9") (pin "2") (pinfunction "2_2") (pintype "passive"))
      (node (ref "PL1") (pin "2") (pinfunction "2_2") (pintype "passive"))
      (node (ref "PL2") (pin "2") (pinfunction "2_2") (pintype "passive"))
      (node (ref "PL3") (pin "2") (pinfunction "2_2") (pintype "passive"))
      (node (ref "PL4") (pin "2") (pinfunction "2_2") (pintype "passive"))
      (node (ref "PL5") (pin "2") (pinfunction "2_2") (pintype "passive"))
    )
    (net (code "3") (name "/PACK3") (class "Default")
      (node (ref "C1") (pin "1") (pinfunction "1_1") (pintype "passive"))
      (node (ref "C1") (pin "2") (pinfunction "2_2") (pintype "passive"))
      (node (ref "C2") (pin "1") (pinfunction "1_1") (pintype "passive"))
      (node (ref "C2") (pin "2") (pinfunction "2_2") (pintype "passive"))
      (node (ref "C3") (pin "1") (pinfunction "1_1") (pintype "passive"))
      (node (ref "C3") (pin "2") (pinfunction "2_2") (pintype "passive"))
      (node (ref "C4") (pin "1") (pinfunction "1_1") (pintype "passive"))
      (node (ref "C4") (pin "2") (pinfunction "2_2") (pintype "passive"))
      (node (ref "C5") (pin "1") (pinfunction "1_1") (pintype "passive"))
      (node (ref "C5") (pin "2") (pinfunction "2_2") (pintype "passive"))
      (node (ref "C6") (pin "1") (pinfunction "1_1") (pintype "passive"))
      (node (ref "C6") (pin "2") (pinfunction "2_2") (pintype "passive"))
      (node (ref "C7") (pin "1") (pinfunction "1_1") (pintype "passive"))
      (node (ref "C7") (pin "2") (pinfunction "2_2") (pintype "passive"))
      (node (ref "C8") (pin "1") (pinfunction "1_1") (pintype "passive"))
      (node (ref "C8") (pin "2") (pinfunction "2_2") (pintype "passive"))
      (node (ref "CC1") (pin "1") (pinfunction "1_1") (pintype "passive"))
      (node (ref "CC1") (pin "2") (pinfunction "2_2") (pintype "passive"))
      (node (ref "CC2") (pin "1") (pinfunction "1_1") (pintype "passive"))
      (node (ref "CC2") (pin "2") (pinfunction "2_2") (pintype "passive"))
      (node (ref "CC3") (pin "1") (pinfunction "1_1") (pintype "passive"))
      (node (ref "CC3") (pin "2") (pinfunction "2_2") (pintype "passive"))
      (node (ref "CC4") (pin "1") (pinfunction "1_1") (pintype "passive"))
      (node (ref "CC4") (pin "2") (pinfunction "2_2") (pintype "passive"))
      (node (ref "CC5") (pin "1") (pinfunction "1_1") (pintype "passive"))
      (node (ref "CC5") (pin "2") (pinfunction "2_2") (pintype "passive"))
      (node (ref "CC6") (pin "1") (pinfunction "1_1") (pintype "passive"))
      (node (ref "CC6") (pin "2") (pinfunction "2_2") (pintype "passive"))
      (node (ref "MDL1") (pin "1") (pinfunction "1_1") (pintype "passive"))
      (node (ref "MDL2") (pin "1") (pinfunction "1_1") (pintype "passive"))
      (node (ref "MDL3") (pin "1") (pinfunction "1_1") (pintype "passive"))
      (node (ref "MDL4") (pin "1") (pinfunction "1_1") (pintype "passive"))
      (node (ref "MDL5") (pin "1") (pinfunction "1_1") (pintype "passive"))
      (node (ref "MDR1") (pin "1") (pinfunction "1_1") (pintype "passive"))
      (node (ref "MDR2") (pin "1") (pinfunction "1_1") (pintype "passive"))
      (node (ref "MDR3") (pin "1") (pinfunction "1_1") (pintype "passive"))
      (node (ref "MDR4") (pin "1") (pinfunction "1_1") (pintype "passive"))
      (node (ref "MDR5") (pin "1") (pinfunction "1_1") (pintype "passive"))
      (node (ref "P1") (pin "1") (pinfunction "1_1") (pintype "passive"))
      (node (ref "P2") (pin "1") (pinfunction "1_1") (pintype "passive"))
      (node (ref "P3") (pin "1") (pinfunction "1_1") (pintype "passive"))
      (node (ref "P4") (pin "1") (pinfunction "1_1") (pintype "passive"))
      (node (ref "P5") (pin "1") (pinfunction "1_1") (pintype "passive"))
      (node (ref "PL1") (pin "1") (pinfunction "1_1") (pintype "passive"))
      (node (ref "PL2") (pin "1") (pinfunction "1_1") (pintype "passive"))
      (node (ref "PL3") (pin "1") (pinfunction "1_1") (pintype "passive"))
      (node (ref "PL4") (pin "1") (pinfunction "1_1") (pintype "passive"))
      (node (ref "PL5") (pin "1") (pinfunction "1_1") (pintype "passive"))
    )
    (net (code "4") (name "Net-(PWR1-Pad1)") (class "Default")
      (node (ref "PWR1") (pin "1") (pinfunction "1_1") (pintype "passive"))
      (node (ref "PWR1") (pin "2") (pinfunction "2_2") (pintype "passive"))
      (node (ref "PWR1") (pin "3") (pinfunction "3_3") (pintype "passive"))
      (node (ref "PWR2") (pin "1") (pinfunction "1_1") (pintype "passive"))
      (node (ref "PWR2") (pin "2") (pinfunction "2_2") (pintype "passive"))
      (node (ref "PWR2") (pin "3") (pinfunction "3_3") (pintype "passive"))
      (node (ref "PWRM1") (pin "1") (pinfunction "1_1") (pintype "passive"))
      (node (ref "PWRM1") (pin "2") (pinfunction "2_2") (pintype "passive"))
      (node (ref "PWRM1") (pin "3") (pinfunction "3_3") (pintype "passive"))
      (node (ref "PWRM2") (pin "1") (pinfunction "1_1") (pintype "passive"))
      (node (ref "PWRM2") (pin "2") (pinfunction "2_2") (pintype "passive"))
      (node (ref "PWRM2") (pin "3") (pinfunction "3_3") (pintype "passive"))
    )
    (net (code "5") (name "Net-(PWR3-Pad1)") (class "Default")
      (node (ref "PWR3") (pin "1") (pinfunction "1_1") (pintype "passive"))
      (node (ref "PWR3") (pin "2") (pinfunction "2_2") (pintype "passive"))
      (node (ref "PWR3") (pin "3") (pinfunction "3_3") (pintype "passive"))
      (node (ref "PWR4") (pin "1") (pinfunction "1_1") (pintype "passive"))
      (node (ref "PWR4") (pin "2") (pinfunction "2_2") (pintype "passive"))
      (node (ref "PWR4") (pin "3") (pinfunction "3_3") (pintype "passive"))
      (node (ref "PWRM3") (pin "1") (pinfunction "1_1") (pintype "passive"))
      (node (ref "PWRM3") (pin "2") (pinfunction "2_2") (pintype "passive"))
      (node (ref "PWRM3") (pin "3") (pinfunction "3_3") (pintype "passive"))
      (node (ref "PWRM4") (pin "1") (pinfunction "1_1") (pintype "passive"))
      (node (ref "PWRM4") (pin "2") (pinfunction "2_2") (pintype "passive"))
      (node (ref "PWRM4") (pin "3") (pinfunction "3_3") (pintype "passive"))
    )
  )
)
